# BSPD_002.net
KiCad netlist of a schematic drawn in Altium Designer
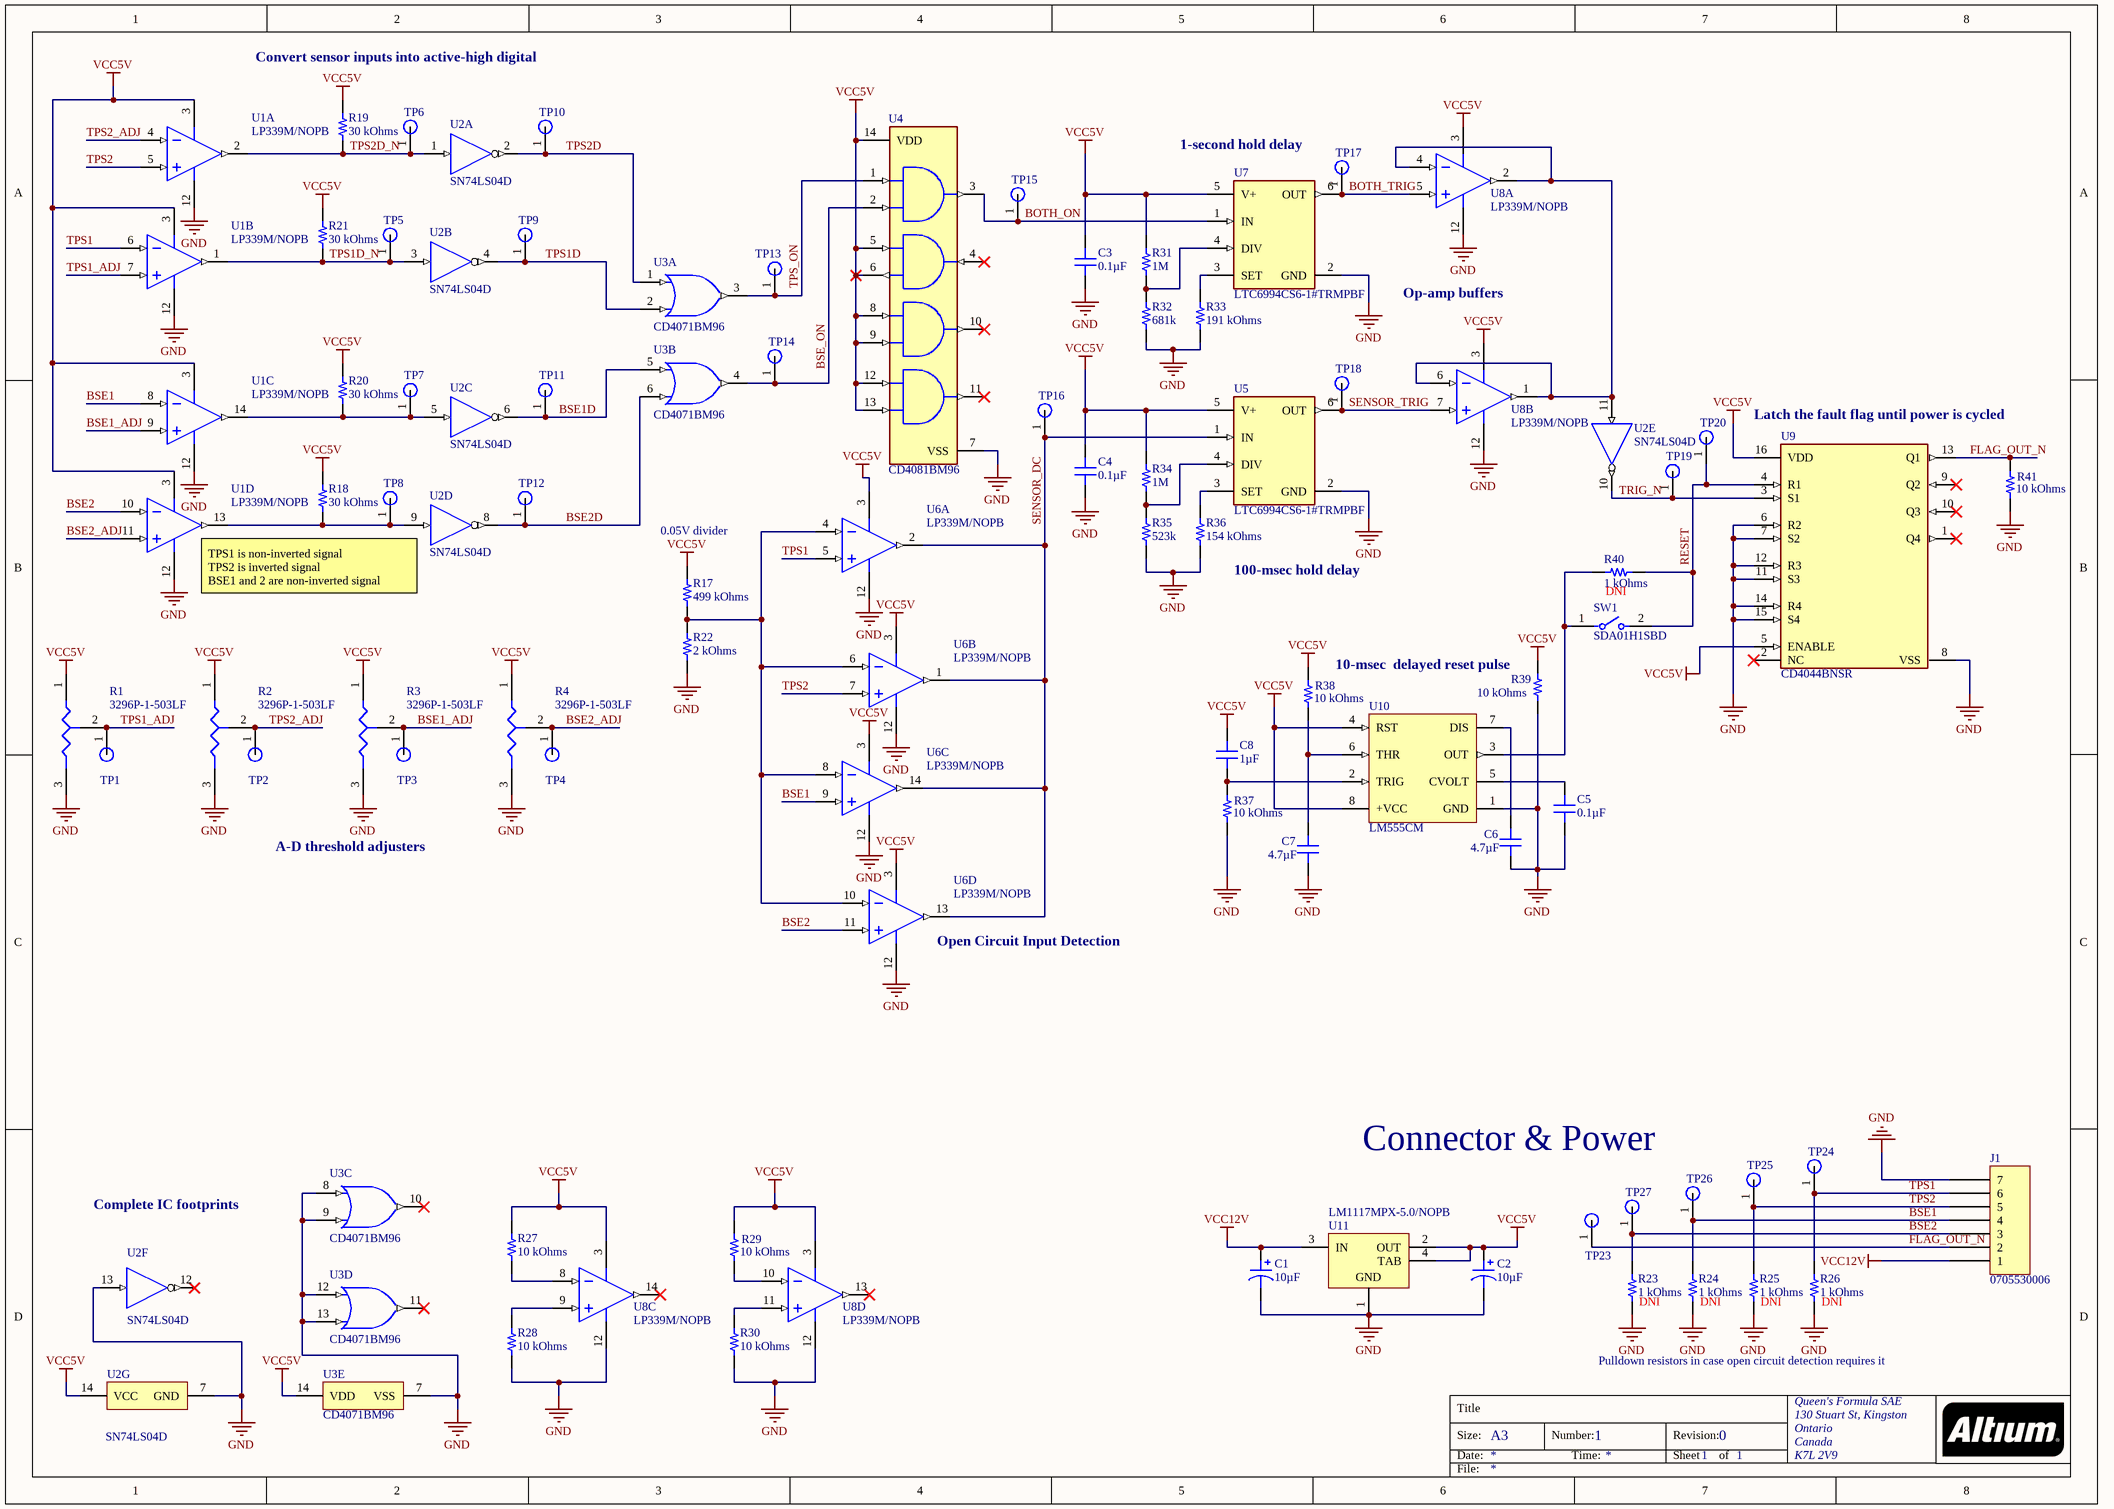
[diagram p0: BSPD_002.SchDoc]

(export (version "E")
  (design (tool "Eeschema 10.0.6"))
  (components
    (comp (ref "C1")
      (value "10µF")
      (footprint "CAP ALSMD 5.3MM H5.4MM")
      (description "CAP ALUM 10UF 20% 50V SMD")
      (fields
        (field (name "PART NUMBER") "EEE-1HA100WR")
        (field (name "MANUFACTURER") "Panasonic Electronic Components")
      )
      (libsource (lib "Celestial Altium Library - altium_library") (part "Polarised Capacitor"))
    )
    (comp (ref "C2")
      (value "10µF")
      (footprint "CAP ALSMD 5.3MM H5.4MM")
      (description "CAP ALUM 10UF 20% 50V SMD")
      (fields
        (field (name "PART NUMBER") "EEE-1HA100WR")
        (field (name "MANUFACTURER") "Panasonic Electronic Components")
      )
      (libsource (lib "Celestial Altium Library - altium_library") (part "Polarised Capacitor"))
    )
    (comp (ref "C3")
      (value "0.1µF")
      (footprint "CAP 0805_2012")
      (description "CAP CER 0.1UF 25V X7R 0805")
      (fields
        (field (name "PART NUMBER") "VJ0805Y104KXXCW1BC")
        (field (name "MANUFACTURER") "Vishay Vitramon")
      )
      (libsource (lib "Celestial Altium Library - altium_library") (part "Capacitor"))
    )
    (comp (ref "C4")
      (value "0.1µF")
      (footprint "CAP 0805_2012")
      (description "CAP CER 0.1UF 25V X7R 0805")
      (fields
        (field (name "PART NUMBER") "VJ0805Y104KXXCW1BC")
        (field (name "MANUFACTURER") "Vishay Vitramon")
      )
      (libsource (lib "Celestial Altium Library - altium_library") (part "Capacitor"))
    )
    (comp (ref "C5")
      (value "0.1µF")
      (footprint "CAP 0805_2012")
      (description "CAP CER 0.1UF 25V X7R 0805")
      (fields
        (field (name "PART NUMBER") "VJ0805Y104KXXCW1BC")
        (field (name "MANUFACTURER") "Vishay Vitramon")
      )
      (libsource (lib "Celestial Altium Library - altium_library") (part "Capacitor"))
    )
    (comp (ref "C6")
      (value "4.7µF")
      (footprint "CAP 0805_2012")
      (description "CAP CER 4.7UF 25V X5R 0805")
      (fields (field (name "PART NUMBER") "TMK212BBJ475KD-T") (field (name "MANUFACTURER") "Taiyo Yuden"))
      (libsource (lib "Celestial Altium Library - altium_library") (part "Capacitor"))
    )
    (comp (ref "C7")
      (value "4.7µF")
      (footprint "CAP 0805_2012")
      (description "CAP CER 4.7UF 25V X5R 0805")
      (fields (field (name "PART NUMBER") "TMK212BBJ475KD-T") (field (name "MANUFACTURER") "Taiyo Yuden"))
      (libsource (lib "Celestial Altium Library - altium_library") (part "Capacitor"))
    )
    (comp (ref "C8")
      (value "1µF")
      (footprint "CAP 0805_2012")
      (description "CAP CER 1UF 25V X7R 0805")
      (fields
        (field (name "PART NUMBER") "VJ0805Y105KXXTW1BC")
        (field (name "MANUFACTURER") "Vishay Vitramon")
      )
      (libsource (lib "Celestial Altium Library - altium_library") (part "Capacitor"))
    )
    (comp (ref "J1")
      (value "0705530006")
      (footprint "MOLEX SDA-70553-7PIN")
      (description "CONN HEADER R/A 7POS 2.54MM")
      (fields (field (name "MANUFACTURER") "Molex"))
      (libsource (lib "Celestial Altium Library - altium_library") (part "7 Pin"))
    )
    (comp (ref "R1")
      (value "3296P-1-503LF")
      (footprint "3296P-1-503LF-Footprint-1")
      (description "50k 10% Trimmer Potentiometer 25-Turn Cermet")
      (fields (field (name "TOLERANCE") "10%"))
      (libsource (lib "Queens University - FSAE") (part "3296P-1-503LF"))
    )
    (comp (ref "R2")
      (value "3296P-1-503LF")
      (footprint "3296P-1-503LF-Footprint-1")
      (description "50k 10% Trimmer Potentiometer 25-Turn Cermet")
      (fields (field (name "TOLERANCE") "10%"))
      (libsource (lib "Queens University - FSAE") (part "3296P-1-503LF"))
    )
    (comp (ref "R3")
      (value "3296P-1-503LF")
      (footprint "3296P-1-503LF-Footprint-1")
      (description "50k 10% Trimmer Potentiometer 25-Turn Cermet")
      (fields (field (name "TOLERANCE") "10%"))
      (libsource (lib "Queens University - FSAE") (part "3296P-1-503LF"))
    )
    (comp (ref "R4")
      (value "3296P-1-503LF")
      (footprint "3296P-1-503LF-Footprint-1")
      (description "50k 10% Trimmer Potentiometer 25-Turn Cermet")
      (fields (field (name "TOLERANCE") "10%"))
      (libsource (lib "Queens University - FSAE") (part "3296P-1-503LF"))
    )
    (comp (ref "R17")
      (value "499 kOhms")
      (footprint "RES 0805_2012")
      (description "RES SMD 499K OHM 1% 1/8W 0805")
      (fields (field (name "PART NUMBER") "RC0805FR-07499KL") (field (name "MANUFACTURER") "Yageo"))
      (libsource (lib "Celestial Altium Library - altium_library") (part "Resistor"))
    )
    (comp (ref "R18")
      (value "30 kOhms")
      (footprint "RES 0805_2012")
      (description "RES SMD 30K OHM 0.5% 1/8W 0805")
      (fields (field (name "PART NUMBER") "RT0805DRD0730KL") (field (name "MANUFACTURER") "Yageo"))
      (libsource (lib "Celestial Altium Library - altium_library") (part "Resistor"))
    )
    (comp (ref "R19")
      (value "30 kOhms")
      (footprint "RES 0805_2012")
      (description "RES SMD 30K OHM 0.5% 1/8W 0805")
      (fields (field (name "PART NUMBER") "RT0805DRD0730KL") (field (name "MANUFACTURER") "Yageo"))
      (libsource (lib "Celestial Altium Library - altium_library") (part "Resistor"))
    )
    (comp (ref "R20")
      (value "30 kOhms")
      (footprint "RES 0805_2012")
      (description "RES SMD 30K OHM 0.5% 1/8W 0805")
      (fields (field (name "PART NUMBER") "RT0805DRD0730KL") (field (name "MANUFACTURER") "Yageo"))
      (libsource (lib "Celestial Altium Library - altium_library") (part "Resistor"))
    )
    (comp (ref "R21")
      (value "30 kOhms")
      (footprint "RES 0805_2012")
      (description "RES SMD 30K OHM 0.5% 1/8W 0805")
      (fields (field (name "PART NUMBER") "RT0805DRD0730KL") (field (name "MANUFACTURER") "Yageo"))
      (libsource (lib "Celestial Altium Library - altium_library") (part "Resistor"))
    )
    (comp (ref "R22")
      (value "2 kOhms")
      (footprint "RES 0805_2012")
      (description "RES SMD 2K OHM 1% 1/8W 0805")
      (fields (field (name "PART NUMBER") "RC0805FR-072KL") (field (name "MANUFACTURER") "Yageo"))
      (libsource (lib "Celestial Altium Library - altium_library") (part "Resistor"))
    )
    (comp (ref "R23")
      (value "1 kOhms")
      (footprint "RES 0805_2012")
      (description "RES 1K OHM 0.1% 1/10W 0805")
      (fields
        (field (name "PART NUMBER") "RNCS0805BKE1K00")
        (field (name "MANUFACTURER") "Stackpole Electronics Inc")
      )
      (libsource (lib "Celestial Altium Library - altium_library") (part "Resistor"))
    )
    (comp (ref "R24")
      (value "1 kOhms")
      (footprint "RES 0805_2012")
      (description "RES 1K OHM 0.1% 1/10W 0805")
      (fields
        (field (name "PART NUMBER") "RNCS0805BKE1K00")
        (field (name "MANUFACTURER") "Stackpole Electronics Inc")
      )
      (libsource (lib "Celestial Altium Library - altium_library") (part "Resistor"))
    )
    (comp (ref "R25")
      (value "1 kOhms")
      (footprint "RES 0805_2012")
      (description "RES 1K OHM 0.1% 1/10W 0805")
      (fields
        (field (name "PART NUMBER") "RNCS0805BKE1K00")
        (field (name "MANUFACTURER") "Stackpole Electronics Inc")
      )
      (libsource (lib "Celestial Altium Library - altium_library") (part "Resistor"))
    )
    (comp (ref "R26")
      (value "1 kOhms")
      (footprint "RES 0805_2012")
      (description "RES 1K OHM 0.1% 1/10W 0805")
      (fields
        (field (name "PART NUMBER") "RNCS0805BKE1K00")
        (field (name "MANUFACTURER") "Stackpole Electronics Inc")
      )
      (libsource (lib "Celestial Altium Library - altium_library") (part "Resistor"))
    )
    (comp (ref "R27")
      (value "10 kOhms")
      (footprint "RES 0805_2012")
      (description "RES SMD 10K OHM 1% 1/8W 0805")
      (fields (field (name "PART NUMBER") "RC0805FR-0710KL") (field (name "MANUFACTURER") "Yageo"))
      (libsource (lib "Celestial Altium Library - altium_library") (part "Resistor"))
    )
    (comp (ref "R28")
      (value "10 kOhms")
      (footprint "RES 0805_2012")
      (description "RES SMD 10K OHM 1% 1/8W 0805")
      (fields (field (name "PART NUMBER") "RC0805FR-0710KL") (field (name "MANUFACTURER") "Yageo"))
      (libsource (lib "Celestial Altium Library - altium_library") (part "Resistor"))
    )
    (comp (ref "R29")
      (value "10 kOhms")
      (footprint "RES 0805_2012")
      (description "RES SMD 10K OHM 1% 1/8W 0805")
      (fields (field (name "PART NUMBER") "RC0805FR-0710KL") (field (name "MANUFACTURER") "Yageo"))
      (libsource (lib "Celestial Altium Library - altium_library") (part "Resistor"))
    )
    (comp (ref "R30")
      (value "10 kOhms")
      (footprint "RES 0805_2012")
      (description "RES SMD 10K OHM 1% 1/8W 0805")
      (fields (field (name "PART NUMBER") "RC0805FR-0710KL") (field (name "MANUFACTURER") "Yageo"))
      (libsource (lib "Celestial Altium Library - altium_library") (part "Resistor"))
    )
    (comp (ref "R31")
      (value "1M")
      (footprint "RES 0805_2012")
      (description "RES SMD 1M OHM 1% 1/8W 0805")
      (fields (field (name "PART NUMBER") "RC0805FR-071ML") (field (name "MANUFACTURER") "Yageo"))
      (libsource (lib "Celestial Altium Library - altium_library") (part "Resistor"))
    )
    (comp (ref "R32")
      (value "681k")
      (footprint "RES 0805_2012")
      (description "RES 681K OHM 1% 1/8W 0805")
      (fields
        (field (name "PART NUMBER") "RMCF0805FT681K")
        (field (name "MANUFACTURER") "Stackpole Electronics Inc")
      )
      (libsource (lib "Celestial Altium Library - altium_library") (part "Resistor"))
    )
    (comp (ref "R33")
      (value "191 kOhms")
      (footprint "RES 0805_2012")
      (description "RES SMD 191K OHM 1% 1/8W 0805")
      (fields (field (name "PART NUMBER") "RC0805FR-07191KL") (field (name "MANUFACTURER") "Yageo"))
      (libsource (lib "Celestial Altium Library - altium_library") (part "Resistor"))
    )
    (comp (ref "R34")
      (value "1M")
      (footprint "RES 0805_2012")
      (description "RES SMD 1M OHM 1% 1/8W 0805")
      (fields (field (name "PART NUMBER") "RC0805FR-071ML") (field (name "MANUFACTURER") "Yageo"))
      (libsource (lib "Celestial Altium Library - altium_library") (part "Resistor"))
    )
    (comp (ref "R35")
      (value "523k")
      (footprint "RES 0805_2012")
      (description "RES SMD 523K OHM 1% 1/8W 0805")
      (fields (field (name "PART NUMBER") "RC0805FR-07523KL") (field (name "MANUFACTURER") "Yageo"))
      (libsource (lib "Celestial Altium Library - altium_library") (part "Resistor"))
    )
    (comp (ref "R36")
      (value "154 kOhms")
      (footprint "RES 0805_2012")
      (description "RES SMD 154K OHM 1% 1/8W 0805")
      (fields (field (name "PART NUMBER") "RC0805FR-07154KL") (field (name "MANUFACTURER") "Yageo"))
      (libsource (lib "Celestial Altium Library - altium_library") (part "Resistor"))
    )
    (comp (ref "R37")
      (value "10 kOhms")
      (footprint "RES 0805_2012")
      (description "RES SMD 10K OHM 1% 1/8W 0805")
      (fields (field (name "PART NUMBER") "RC0805FR-0710KL") (field (name "MANUFACTURER") "Yageo"))
      (libsource (lib "Celestial Altium Library - altium_library") (part "Resistor"))
    )
    (comp (ref "R38")
      (value "10 kOhms")
      (footprint "RES 0805_2012")
      (description "RES SMD 10K OHM 1% 1/8W 0805")
      (fields (field (name "PART NUMBER") "RC0805FR-0710KL") (field (name "MANUFACTURER") "Yageo"))
      (libsource (lib "Celestial Altium Library - altium_library") (part "Resistor"))
    )
    (comp (ref "R39")
      (value "10 kOhms")
      (footprint "RES 0805_2012")
      (description "RES SMD 10K OHM 1% 1/8W 0805")
      (fields (field (name "PART NUMBER") "RC0805FR-0710KL") (field (name "MANUFACTURER") "Yageo"))
      (libsource (lib "Celestial Altium Library - altium_library") (part "Resistor"))
    )
    (comp (ref "R40")
      (value "1 kOhms")
      (footprint "RES 0805_2012")
      (description "RES 1K OHM 0.1% 1/10W 0805")
      (fields
        (field (name "PART NUMBER") "RNCS0805BKE1K00")
        (field (name "MANUFACTURER") "Stackpole Electronics Inc")
      )
      (libsource (lib "Celestial Altium Library - altium_library") (part "Resistor"))
    )
    (comp (ref "R41")
      (value "10 kOhms")
      (footprint "RES 0805_2012")
      (description "RES SMD 10K OHM 1% 1/8W 0805")
      (fields (field (name "PART NUMBER") "RC0805FR-0710KL") (field (name "MANUFACTURER") "Yageo"))
      (libsource (lib "Celestial Altium Library - altium_library") (part "Resistor"))
    )
    (comp (ref "SW1")
      (value "SDA01H1SBD")
      (footprint "FP-SDA01H1SBD-MFG")
      (description "Switch DIP OFF ON SPST 1 Raised Slide 0.1A 24VDC Gull Wing 1000Cycles SMD Tube")
      (libsource (lib "Queens University - FSAE") (part "bb27bde45df87f1f469753f287ef5ae"))
    )
    (comp (ref "TP1") (value "Test Point") (footprint "TP1") (libsource (lib "ethan") (part "TP1")))
    (comp (ref "TP2") (value "Test Point") (footprint "TP1") (libsource (lib "ethan") (part "TP1")))
    (comp (ref "TP3") (value "Test Point") (footprint "TP1") (libsource (lib "ethan") (part "TP1")))
    (comp (ref "TP4") (value "Test Point") (footprint "TP1") (libsource (lib "ethan") (part "TP1")))
    (comp (ref "TP5") (value "Test Point") (footprint "TP1") (libsource (lib "ethan") (part "TP1")))
    (comp (ref "TP6") (value "Test Point") (footprint "TP1") (libsource (lib "ethan") (part "TP1")))
    (comp (ref "TP7") (value "Test Point") (footprint "TP1") (libsource (lib "ethan") (part "TP1")))
    (comp (ref "TP8") (value "Test Point") (footprint "TP1") (libsource (lib "ethan") (part "TP1")))
    (comp (ref "TP9") (value "Test Point") (footprint "TP1") (libsource (lib "ethan") (part "TP1")))
    (comp (ref "TP10") (value "Test Point") (footprint "TP1") (libsource (lib "ethan") (part "TP1")))
    (comp (ref "TP11") (value "Test Point") (footprint "TP1") (libsource (lib "ethan") (part "TP1")))
    (comp (ref "TP12") (value "Test Point") (footprint "TP1") (libsource (lib "ethan") (part "TP1")))
    (comp (ref "TP13") (value "Test Point") (footprint "TP1") (libsource (lib "ethan") (part "TP1")))
    (comp (ref "TP14") (value "Test Point") (footprint "TP1") (libsource (lib "ethan") (part "TP1")))
    (comp (ref "TP15") (value "Test Point") (footprint "TP1") (libsource (lib "ethan") (part "TP1")))
    (comp (ref "TP16") (value "Test Point") (footprint "TP1") (libsource (lib "ethan") (part "TP1")))
    (comp (ref "TP17") (value "Test Point") (footprint "TP1") (libsource (lib "ethan") (part "TP1")))
    (comp (ref "TP18") (value "Test Point") (footprint "TP1") (libsource (lib "ethan") (part "TP1")))
    (comp (ref "TP19") (value "Test Point") (footprint "TP1") (libsource (lib "ethan") (part "TP1")))
    (comp (ref "TP20") (value "Test Point") (footprint "TP1") (libsource (lib "ethan") (part "TP1")))
    (comp (ref "TP23") (value "Test Point") (footprint "TP1") (libsource (lib "ethan") (part "TP1")))
    (comp (ref "TP24") (value "Test Point") (footprint "TP1") (libsource (lib "ethan") (part "TP1")))
    (comp (ref "TP25") (value "Test Point") (footprint "TP1") (libsource (lib "ethan") (part "TP1")))
    (comp (ref "TP26") (value "Test Point") (footprint "TP1") (libsource (lib "ethan") (part "TP1")))
    (comp (ref "TP27") (value "Test Point") (footprint "TP1") (libsource (lib "ethan") (part "TP1")))
    (comp (ref "U1")
      (value "LP339M/NOPB")
      (footprint "D0014A_L")
      (description "TEXAS INSTRUMENTS   LP339M/NOPB   LOW POWER COMPARATOR, QUAD, 8 uS, SOIC-14")
      (libsource (lib "Queens University - FSAE") (part "AN-COMP-LP339-14"))
    )
    (comp (ref "U2")
      (value "SN74LS04D")
      (footprint "D0014A_L")
      (description "TEXAS INSTRUMENTS - SN74LS04D - HEX INVERTER, SMD, 74LS04, SOIC14")
      (libsource (lib "Queens University - FSAE") (part "TI-CD_SNX4XXXXXX4X_19A-14"))
    )
    (comp (ref "U3")
      (value "CD4071BM96")
      (footprint "D0014A_L")
      (description "OR Gate 4-Element 2-IN CMOS 14-Pin SOIC T/R")
      (libsource (lib "Queens University - FSAE") (part "TI-CD4071B-14"))
    )
    (comp (ref "U4")
      (value "CD4081BM96")
      (footprint "FP-D0014A-MFG")
      (description "TEXAS INSTRUMENTS - CD4081BM96 - AND Gate, CD4081, 8 Input, 6.8 mA, 3 V to 18 V, SOIC-14")
      (libsource (lib "Queens University - FSAE") (part "72f76806fbbab040b8a954f50d4bcdd"))
    )
    (comp (ref "U5")
      (value "LTC6994CS6-1#TRMPBF")
      (footprint "FP-S6-6-05-08-1636-MFG")
      (description "Programmable Delay Block 6-Pin TSOT-23 T/R")
      (libsource (lib "Queens University - FSAE") (part "9980ea3ec28f5fc7ab7b696581a065a"))
    )
    (comp (ref "U6")
      (value "LP339M/NOPB")
      (footprint "D0014A_L")
      (description "TEXAS INSTRUMENTS   LP339M/NOPB   LOW POWER COMPARATOR, QUAD, 8 uS, SOIC-14")
      (libsource (lib "Queens University - FSAE") (part "AN-COMP-LP339-14"))
    )
    (comp (ref "U7")
      (value "LTC6994CS6-1#TRMPBF")
      (footprint "FP-S6-6-05-08-1636-MFG")
      (description "Programmable Delay Block 6-Pin TSOT-23 T/R")
      (libsource (lib "Queens University - FSAE") (part "9980ea3ec28f5fc7ab7b696581a065a"))
    )
    (comp (ref "U8")
      (value "LP339M/NOPB")
      (footprint "D0014A_L")
      (description "TEXAS INSTRUMENTS   LP339M/NOPB   LOW POWER COMPARATOR, QUAD, 8 uS, SOIC-14")
      (libsource (lib "Queens University - FSAE") (part "AN-COMP-LP339-14"))
    )
    (comp (ref "U9")
      (value "CD4044BNSR")
      (footprint "FP-D0016A-MFG")
      (libsource (lib "Queens University - FSAE") (part "b654bc9f5570033e531f2d9d884d1b2"))
    )
    (comp (ref "U10")
      (value "LM555CM")
      (footprint "D0008A_L")
      (description "IC OSC SGL TIMER 100KHZ 8-SOIC")
      (libsource (lib "Queens University - FSAE") (part "AN-TIMER-LM555-8"))
    )
    (comp (ref "U11")
      (value "LM1117MPX-5.0/NOPB")
      (footprint "DCY0004A_M")
      (description "800-mA 15-V linear voltage regulator 4-SOT-223 0 to 125")
      (libsource (lib "Queens University - FSAE") (part "PM-REG-LM1086-SOT4"))
    )
  )
  (nets
    (net (code "1") (name "/BOTH_ON") (class "Default")
      (node (ref "TP15") (pin "1") (pinfunction "1_1") (pintype "passive"))
      (node (ref "U4") (pin "3") (pinfunction "J_3") (pintype "output"))
      (node (ref "U7") (pin "1") (pinfunction "IN_1") (pintype "input"))
    )
    (net (code "2") (name "/BOTH_TRIG") (class "Default")
      (node (ref "TP17") (pin "1") (pinfunction "1_1") (pintype "passive"))
      (node (ref "U7") (pin "6") (pinfunction "OUT_6") (pintype "output"))
      (node (ref "U8") (pin "5") (pinfunction "IN1+_5") (pintype "input"))
    )
    (net (code "3") (name "/BSE1") (class "Default")
      (node (ref "J1") (pin "4") (pinfunction "4_4") (pintype "passive"))
      (node (ref "R24") (pin "2") (pinfunction "2_2") (pintype "passive"))
      (node (ref "TP26") (pin "1") (pinfunction "1_1") (pintype "passive"))
      (node (ref "U1") (pin "8") (pinfunction "IN3-_8") (pintype "input"))
      (node (ref "U6") (pin "9") (pinfunction "IN3+_9") (pintype "input"))
    )
    (net (code "4") (name "/BSE1D") (class "Default")
      (node (ref "TP11") (pin "1") (pinfunction "1_1") (pintype "passive"))
      (node (ref "U2") (pin "6") (pinfunction "~{3Y}_6") (pintype "output"))
      (node (ref "U3") (pin "5") (pinfunction "C_5") (pintype "input"))
    )
    (net (code "5") (name "/BSE1_ADJ") (class "Default")
      (node (ref "R3") (pin "2") (pinfunction "TAP_2") (pintype "passive"))
      (node (ref "TP3") (pin "1") (pinfunction "1_1") (pintype "passive"))
      (node (ref "U1") (pin "9") (pinfunction "IN3+_9") (pintype "input"))
    )
    (net (code "6") (name "/BSE2") (class "Default")
      (node (ref "J1") (pin "3") (pinfunction "3_3") (pintype "passive"))
      (node (ref "R23") (pin "2") (pinfunction "2_2") (pintype "passive"))
      (node (ref "TP27") (pin "1") (pinfunction "1_1") (pintype "passive"))
      (node (ref "U1") (pin "10") (pinfunction "IN4-_10") (pintype "input"))
      (node (ref "U6") (pin "11") (pinfunction "IN4+_11") (pintype "input"))
    )
    (net (code "7") (name "/BSE2D") (class "Default")
      (node (ref "TP12") (pin "1") (pinfunction "1_1") (pintype "passive"))
      (node (ref "U2") (pin "8") (pinfunction "~{4Y}_8") (pintype "output"))
      (node (ref "U3") (pin "6") (pinfunction "D_6") (pintype "input"))
    )
    (net (code "8") (name "/BSE2_ADJ") (class "Default")
      (node (ref "R4") (pin "2") (pinfunction "TAP_2") (pintype "passive"))
      (node (ref "TP4") (pin "1") (pinfunction "1_1") (pintype "passive"))
      (node (ref "U1") (pin "11") (pinfunction "IN4+_11") (pintype "input"))
    )
    (net (code "9") (name "/BSE_ON") (class "Default")
      (node (ref "TP14") (pin "1") (pinfunction "1_1") (pintype "passive"))
      (node (ref "U3") (pin "4") (pinfunction "K_4") (pintype "output"))
      (node (ref "U4") (pin "2") (pinfunction "B_2") (pintype "input"))
    )
    (net (code "10") (name "/FLAG_OUT_N") (class "Default")
      (node (ref "J1") (pin "2") (pinfunction "2_2") (pintype "passive"))
      (node (ref "R41") (pin "2") (pinfunction "2_2") (pintype "passive"))
      (node (ref "TP23") (pin "1") (pinfunction "1_1") (pintype "passive"))
      (node (ref "U9") (pin "13") (pinfunction "Q1_13") (pintype "output"))
    )
    (net (code "11") (name "/RESET") (class "Default")
      (node (ref "R40") (pin "1") (pinfunction "1_1") (pintype "passive"))
      (node (ref "SW1") (pin "2") (pinfunction "2_2") (pintype "passive"))
      (node (ref "TP20") (pin "1") (pinfunction "1_1") (pintype "passive"))
      (node (ref "U9") (pin "4") (pinfunction "R1_4") (pintype "input"))
    )
    (net (code "12") (name "/SENSOR_DC") (class "Default")
      (node (ref "TP16") (pin "1") (pinfunction "1_1") (pintype "passive"))
      (node (ref "U5") (pin "1") (pinfunction "IN_1") (pintype "input"))
      (node (ref "U6") (pin "1") (pinfunction "OUT2_1") (pintype "output"))
      (node (ref "U6") (pin "13") (pinfunction "OUT4_13") (pintype "output"))
      (node (ref "U6") (pin "14") (pinfunction "OUT3_14") (pintype "output"))
      (node (ref "U6") (pin "2") (pinfunction "OUT1_2") (pintype "output"))
    )
    (net (code "13") (name "/SENSOR_TRIG") (class "Default")
      (node (ref "TP18") (pin "1") (pinfunction "1_1") (pintype "passive"))
      (node (ref "U5") (pin "6") (pinfunction "OUT_6") (pintype "output"))
      (node (ref "U8") (pin "7") (pinfunction "IN2+_7") (pintype "input"))
    )
    (net (code "14") (name "/TPS1") (class "Default")
      (node (ref "J1") (pin "6") (pinfunction "6_6") (pintype "passive"))
      (node (ref "R26") (pin "2") (pinfunction "2_2") (pintype "passive"))
      (node (ref "TP24") (pin "1") (pinfunction "1_1") (pintype "passive"))
      (node (ref "U1") (pin "6") (pinfunction "IN2-_6") (pintype "input"))
      (node (ref "U6") (pin "5") (pinfunction "IN1+_5") (pintype "input"))
    )
    (net (code "15") (name "/TPS1D") (class "Default")
      (node (ref "TP9") (pin "1") (pinfunction "1_1") (pintype "passive"))
      (node (ref "U2") (pin "4") (pinfunction "~{2Y}_4") (pintype "output"))
      (node (ref "U3") (pin "2") (pinfunction "B_2") (pintype "input"))
    )
    (net (code "16") (name "/TPS1D_N") (class "Default")
      (node (ref "R21") (pin "1") (pinfunction "1_1") (pintype "passive"))
      (node (ref "TP5") (pin "1") (pinfunction "1_1") (pintype "passive"))
      (node (ref "U1") (pin "1") (pinfunction "OUT2_1") (pintype "output"))
      (node (ref "U2") (pin "3") (pinfunction "2A_3") (pintype "input"))
    )
    (net (code "17") (name "/TPS1_ADJ") (class "Default")
      (node (ref "R1") (pin "2") (pinfunction "TAP_2") (pintype "passive"))
      (node (ref "TP1") (pin "1") (pinfunction "1_1") (pintype "passive"))
      (node (ref "U1") (pin "7") (pinfunction "IN2+_7") (pintype "input"))
    )
    (net (code "18") (name "/TPS2") (class "Default")
      (node (ref "J1") (pin "5") (pinfunction "5_5") (pintype "passive"))
      (node (ref "R25") (pin "2") (pinfunction "2_2") (pintype "passive"))
      (node (ref "TP25") (pin "1") (pinfunction "1_1") (pintype "passive"))
      (node (ref "U1") (pin "5") (pinfunction "IN1+_5") (pintype "input"))
      (node (ref "U6") (pin "7") (pinfunction "IN2+_7") (pintype "input"))
    )
    (net (code "19") (name "/TPS2D") (class "Default")
      (node (ref "TP10") (pin "1") (pinfunction "1_1") (pintype "passive"))
      (node (ref "U2") (pin "2") (pinfunction "~{1Y}_2") (pintype "output"))
      (node (ref "U3") (pin "1") (pinfunction "A_1") (pintype "input"))
    )
    (net (code "20") (name "/TPS2D_N") (class "Default")
      (node (ref "R19") (pin "1") (pinfunction "1_1") (pintype "passive"))
      (node (ref "TP6") (pin "1") (pinfunction "1_1") (pintype "passive"))
      (node (ref "U1") (pin "2") (pinfunction "OUT1_2") (pintype "output"))
      (node (ref "U2") (pin "1") (pinfunction "1A_1") (pintype "input"))
    )
    (net (code "21") (name "/TPS2_ADJ") (class "Default")
      (node (ref "R2") (pin "2") (pinfunction "TAP_2") (pintype "passive"))
      (node (ref "TP2") (pin "1") (pinfunction "1_1") (pintype "passive"))
      (node (ref "U1") (pin "4") (pinfunction "IN1-_4") (pintype "input"))
    )
    (net (code "22") (name "/TPS_ON") (class "Default")
      (node (ref "TP13") (pin "1") (pinfunction "1_1") (pintype "passive"))
      (node (ref "U3") (pin "3") (pinfunction "J_3") (pintype "output"))
      (node (ref "U4") (pin "1") (pinfunction "A_1") (pintype "input"))
    )
    (net (code "23") (name "/TRIG_N") (class "Default")
      (node (ref "TP19") (pin "1") (pinfunction "1_1") (pintype "passive"))
      (node (ref "U2") (pin "10") (pinfunction "~{5Y}_10") (pintype "output"))
      (node (ref "U9") (pin "3") (pinfunction "S1_3") (pintype "input"))
    )
    (net (code "24") (name "GND") (class "Default")
      (node (ref "C1") (pin "2") (pinfunction "2_2") (pintype "passive"))
      (node (ref "C2") (pin "2") (pinfunction "2_2") (pintype "passive"))
      (node (ref "C3") (pin "1") (pinfunction "1_1") (pintype "passive"))
      (node (ref "C4") (pin "1") (pinfunction "1_1") (pintype "passive"))
      (node (ref "C5") (pin "1") (pinfunction "1_1") (pintype "passive"))
      (node (ref "C6") (pin "2") (pinfunction "2_2") (pintype "passive"))
      (node (ref "C7") (pin "2") (pinfunction "2_2") (pintype "passive"))
      (node (ref "J1") (pin "7") (pinfunction "7_7") (pintype "passive"))
      (node (ref "R1") (pin "3") (pinfunction "B_3") (pintype "passive"))
      (node (ref "R2") (pin "3") (pinfunction "B_3") (pintype "passive"))
      (node (ref "R22") (pin "1") (pinfunction "1_1") (pintype "passive"))
      (node (ref "R23") (pin "1") (pinfunction "1_1") (pintype "passive"))
      (node (ref "R24") (pin "1") (pinfunction "1_1") (pintype "passive"))
      (node (ref "R25") (pin "1") (pinfunction "1_1") (pintype "passive"))
      (node (ref "R26") (pin "1") (pinfunction "1_1") (pintype "passive"))
      (node (ref "R28") (pin "1") (pinfunction "1_1") (pintype "passive"))
      (node (ref "R3") (pin "3") (pinfunction "B_3") (pintype "passive"))
      (node (ref "R30") (pin "1") (pinfunction "1_1") (pintype "passive"))
      (node (ref "R32") (pin "1") (pinfunction "1_1") (pintype "passive"))
      (node (ref "R33") (pin "1") (pinfunction "1_1") (pintype "passive"))
      (node (ref "R35") (pin "1") (pinfunction "1_1") (pintype "passive"))
      (node (ref "R36") (pin "1") (pinfunction "1_1") (pintype "passive"))
      (node (ref "R37") (pin "1") (pinfunction "1_1") (pintype "passive"))
      (node (ref "R39") (pin "1") (pinfunction "1_1") (pintype "passive"))
      (node (ref "R4") (pin "3") (pinfunction "B_3") (pintype "passive"))
      (node (ref "R41") (pin "1") (pinfunction "1_1") (pintype "passive"))
      (node (ref "U1") (pin "12") (pinfunction "GND_12") (pintype "power_in"))
      (node (ref "U10") (pin "1") (pinfunction "GND_1") (pintype "power_in"))
      (node (ref "U11") (pin "1") (pinfunction "GND_1") (pintype "power_in"))
      (node (ref "U2") (pin "13") (pinfunction "6A_13") (pintype "input"))
      (node (ref "U2") (pin "7") (pinfunction "GND_7") (pintype "power_in"))
      (node (ref "U3") (pin "12") (pinfunction "G_12") (pintype "input"))
      (node (ref "U3") (pin "13") (pinfunction "H_13") (pintype "input"))
      (node (ref "U3") (pin "7") (pinfunction "VSS_7") (pintype "power_in"))
      (node (ref "U3") (pin "8") (pinfunction "E_8") (pintype "input"))
      (node (ref "U3") (pin "9") (pinfunction "F_9") (pintype "input"))
      (node (ref "U4") (pin "7") (pinfunction "VSS_7") (pintype "power_in"))
      (node (ref "U5") (pin "2") (pinfunction "GND_2") (pintype "power_in"))
      (node (ref "U6") (pin "12") (pinfunction "GND_12") (pintype "power_in"))
      (node (ref "U7") (pin "2") (pinfunction "GND_2") (pintype "power_in"))
      (node (ref "U8") (pin "12") (pinfunction "GND_12") (pintype "power_in"))
      (node (ref "U9") (pin "11") (pinfunction "S3_11") (pintype "input"))
      (node (ref "U9") (pin "12") (pinfunction "R3_12") (pintype "input"))
      (node (ref "U9") (pin "14") (pinfunction "R4_14") (pintype "input"))
      (node (ref "U9") (pin "15") (pinfunction "S4_15") (pintype "input"))
      (node (ref "U9") (pin "6") (pinfunction "R2_6") (pintype "input"))
      (node (ref "U9") (pin "7") (pinfunction "S2_7") (pintype "input"))
      (node (ref "U9") (pin "8") (pinfunction "VSS_8") (pintype "power_in"))
    )
    (net (code "25") (name "Net-(U1C-OUT3)") (class "Default")
      (node (ref "R20") (pin "1") (pinfunction "1_1") (pintype "passive"))
      (node (ref "TP7") (pin "1") (pinfunction "1_1") (pintype "passive"))
      (node (ref "U1") (pin "14") (pinfunction "OUT3_14") (pintype "output"))
      (node (ref "U2") (pin "5") (pinfunction "3A_5") (pintype "input"))
    )
    (net (code "26") (name "Net-(U1D-OUT4)") (class "Default")
      (node (ref "R18") (pin "1") (pinfunction "1_1") (pintype "passive"))
      (node (ref "TP8") (pin "1") (pinfunction "1_1") (pintype "passive"))
      (node (ref "U1") (pin "13") (pinfunction "OUT4_13") (pintype "output"))
      (node (ref "U2") (pin "9") (pinfunction "4A_9") (pintype "input"))
    )
    (net (code "27") (name "Net-(U2E-5A)") (class "Default")
      (node (ref "U2") (pin "11") (pinfunction "5A_11") (pintype "input"))
      (node (ref "U8") (pin "1") (pinfunction "OUT2_1") (pintype "output"))
      (node (ref "U8") (pin "2") (pinfunction "OUT1_2") (pintype "output"))
      (node (ref "U8") (pin "4") (pinfunction "IN1-_4") (pintype "input"))
      (node (ref "U8") (pin "6") (pinfunction "IN2-_6") (pintype "input"))
    )
    (net (code "28") (name "Net-(U5-DIV)") (class "Default")
      (node (ref "R34") (pin "2") (pinfunction "2_2") (pintype "passive"))
      (node (ref "R35") (pin "2") (pinfunction "2_2") (pintype "passive"))
      (node (ref "U5") (pin "4") (pinfunction "DIV_4") (pintype "input"))
    )
    (net (code "29") (name "Net-(U5-SET)") (class "Default")
      (node (ref "R36") (pin "2") (pinfunction "2_2") (pintype "passive"))
      (node (ref "U5") (pin "3") (pinfunction "SET_3") (pintype "passive"))
    )
    (net (code "30") (name "Net-(U6A-IN1-)") (class "Default")
      (node (ref "R17") (pin "1") (pinfunction "1_1") (pintype "passive"))
      (node (ref "R22") (pin "2") (pinfunction "2_2") (pintype "passive"))
      (node (ref "U6") (pin "10") (pinfunction "IN4-_10") (pintype "input"))
      (node (ref "U6") (pin "4") (pinfunction "IN1-_4") (pintype "input"))
      (node (ref "U6") (pin "6") (pinfunction "IN2-_6") (pintype "input"))
      (node (ref "U6") (pin "8") (pinfunction "IN3-_8") (pintype "input"))
    )
    (net (code "31") (name "Net-(U7-DIV)") (class "Default")
      (node (ref "R31") (pin "2") (pinfunction "2_2") (pintype "passive"))
      (node (ref "R32") (pin "2") (pinfunction "2_2") (pintype "passive"))
      (node (ref "U7") (pin "4") (pinfunction "DIV_4") (pintype "input"))
    )
    (net (code "32") (name "Net-(U7-SET)") (class "Default")
      (node (ref "R33") (pin "2") (pinfunction "2_2") (pintype "passive"))
      (node (ref "U7") (pin "3") (pinfunction "SET_3") (pintype "passive"))
    )
    (net (code "33") (name "Net-(U8C-IN3+)") (class "Default")
      (node (ref "R28") (pin "2") (pinfunction "2_2") (pintype "passive"))
      (node (ref "U8") (pin "9") (pinfunction "IN3+_9") (pintype "input"))
    )
    (net (code "34") (name "Net-(U8C-IN3-)") (class "Default")
      (node (ref "R27") (pin "1") (pinfunction "1_1") (pintype "passive"))
      (node (ref "U8") (pin "8") (pinfunction "IN3-_8") (pintype "input"))
    )
    (net (code "35") (name "Net-(U8D-IN4+)") (class "Default")
      (node (ref "R30") (pin "2") (pinfunction "2_2") (pintype "passive"))
      (node (ref "U8") (pin "11") (pinfunction "IN4+_11") (pintype "input"))
    )
    (net (code "36") (name "Net-(U8D-IN4-)") (class "Default")
      (node (ref "R29") (pin "1") (pinfunction "1_1") (pintype "passive"))
      (node (ref "U8") (pin "10") (pinfunction "IN4-_10") (pintype "input"))
    )
    (net (code "37") (name "Net-(U10-CVOLT)") (class "Default")
      (node (ref "C5") (pin "2") (pinfunction "2_2") (pintype "passive"))
      (node (ref "U10") (pin "5") (pinfunction "CVOLT_5") (pintype "passive"))
    )
    (net (code "38") (name "Net-(U10-DIS)") (class "Default")
      (node (ref "C6") (pin "1") (pinfunction "1_1") (pintype "passive"))
      (node (ref "U10") (pin "7") (pinfunction "DIS_7") (pintype "open_collector"))
    )
    (net (code "39") (name "Net-(U10-OUT)") (class "Default")
      (node (ref "R40") (pin "2") (pinfunction "2_2") (pintype "passive"))
      (node (ref "SW1") (pin "1") (pinfunction "1_1") (pintype "passive"))
      (node (ref "U10") (pin "3") (pinfunction "OUT_3") (pintype "output"))
    )
    (net (code "40") (name "Net-(U10-THR)") (class "Default")
      (node (ref "C7") (pin "1") (pinfunction "1_1") (pintype "passive"))
      (node (ref "R38") (pin "1") (pinfunction "1_1") (pintype "passive"))
      (node (ref "U10") (pin "6") (pinfunction "THR_6") (pintype "input"))
    )
    (net (code "41") (name "Net-(U10-TRIG)") (class "Default")
      (node (ref "C8") (pin "1") (pinfunction "1_1") (pintype "passive"))
      (node (ref "R37") (pin "2") (pinfunction "2_2") (pintype "passive"))
      (node (ref "U10") (pin "2") (pinfunction "TRIG_2") (pintype "input"))
    )
    (net (code "42") (name "VCC5V") (class "Default")
      (node (ref "C2") (pin "1") (pinfunction "1_1") (pintype "passive"))
      (node (ref "C3") (pin "2") (pinfunction "2_2") (pintype "passive"))
      (node (ref "C4") (pin "2") (pinfunction "2_2") (pintype "passive"))
      (node (ref "C8") (pin "2") (pinfunction "2_2") (pintype "passive"))
      (node (ref "R1") (pin "1") (pinfunction "A_1") (pintype "passive"))
      (node (ref "R17") (pin "2") (pinfunction "2_2") (pintype "passive"))
      (node (ref "R18") (pin "2") (pinfunction "2_2") (pintype "passive"))
      (node (ref "R19") (pin "2") (pinfunction "2_2") (pintype "passive"))
      (node (ref "R2") (pin "1") (pinfunction "A_1") (pintype "passive"))
      (node (ref "R20") (pin "2") (pinfunction "2_2") (pintype "passive"))
      (node (ref "R21") (pin "2") (pinfunction "2_2") (pintype "passive"))
      (node (ref "R27") (pin "2") (pinfunction "2_2") (pintype "passive"))
      (node (ref "R29") (pin "2") (pinfunction "2_2") (pintype "passive"))
      (node (ref "R3") (pin "1") (pinfunction "A_1") (pintype "passive"))
      (node (ref "R31") (pin "1") (pinfunction "1_1") (pintype "passive"))
      (node (ref "R34") (pin "1") (pinfunction "1_1") (pintype "passive"))
      (node (ref "R38") (pin "2") (pinfunction "2_2") (pintype "passive"))
      (node (ref "R39") (pin "2") (pinfunction "2_2") (pintype "passive"))
      (node (ref "R4") (pin "1") (pinfunction "A_1") (pintype "passive"))
      (node (ref "U1") (pin "3") (pinfunction "V+_3") (pintype "power_in"))
      (node (ref "U10") (pin "4") (pinfunction "RST_4") (pintype "input"))
      (node (ref "U10") (pin "8") (pinfunction "+VCC_8") (pintype "power_in"))
      (node (ref "U11") (pin "2") (pinfunction "OUT_2") (pintype "power_in"))
      (node (ref "U11") (pin "4") (pinfunction "TAB_4") (pintype "power_in"))
      (node (ref "U2") (pin "14") (pinfunction "VCC_14") (pintype "power_in"))
      (node (ref "U3") (pin "14") (pinfunction "VDD_14") (pintype "power_in"))
      (node (ref "U4") (pin "12") (pinfunction "G_12") (pintype "input"))
      (node (ref "U4") (pin "13") (pinfunction "H_13") (pintype "input"))
      (node (ref "U4") (pin "14") (pinfunction "VDD_14") (pintype "power_in"))
      (node (ref "U4") (pin "5") (pinfunction "C_5") (pintype "input"))
      (node (ref "U4") (pin "6") (pinfunction "D_6") (pintype "output"))
      (node (ref "U4") (pin "8") (pinfunction "E_8") (pintype "input"))
      (node (ref "U4") (pin "9") (pinfunction "F_9") (pintype "input"))
      (node (ref "U5") (pin "5") (pinfunction "V+_5") (pintype "power_in"))
      (node (ref "U6") (pin "3") (pinfunction "V+_3") (pintype "power_in"))
      (node (ref "U7") (pin "5") (pinfunction "V+_5") (pintype "power_in"))
      (node (ref "U8") (pin "3") (pinfunction "V+_3") (pintype "power_in"))
      (node (ref "U9") (pin "16") (pinfunction "VDD_16") (pintype "power_in"))
      (node (ref "U9") (pin "5") (pinfunction "ENABLE_5") (pintype "input"))
    )
    (net (code "43") (name "VCC12V") (class "Default")
      (node (ref "C1") (pin "1") (pinfunction "1_1") (pintype "passive"))
      (node (ref "J1") (pin "1") (pinfunction "1_1") (pintype "passive"))
      (node (ref "U11") (pin "3") (pinfunction "IN_3") (pintype "power_in"))
    )
    (net (code "44") (name "unconnected-(U2F-~{6Y}-Pad12)") (class "Default")
      (node (ref "U2") (pin "12") (pinfunction "~{6Y}_12") (pintype "output+no_connect"))
    )
    (net (code "45") (name "unconnected-(U3C-L-Pad10)") (class "Default")
      (node (ref "U3") (pin "10") (pinfunction "L_10") (pintype "output+no_connect"))
    )
    (net (code "46") (name "unconnected-(U3D-M-Pad11)") (class "Default")
      (node (ref "U3") (pin "11") (pinfunction "M_11") (pintype "output+no_connect"))
    )
    (net (code "47") (name "unconnected-(U4-K-Pad4)") (class "Default")
      (node (ref "U4") (pin "4") (pinfunction "K_4") (pintype "input+no_connect"))
    )
    (net (code "48") (name "unconnected-(U4-L-Pad10)") (class "Default")
      (node (ref "U4") (pin "10") (pinfunction "L_10") (pintype "output+no_connect"))
    )
    (net (code "49") (name "unconnected-(U4-M-Pad11)") (class "Default")
      (node (ref "U4") (pin "11") (pinfunction "M_11") (pintype "output+no_connect"))
    )
    (net (code "50") (name "unconnected-(U8C-OUT3-Pad14)") (class "Default")
      (node (ref "U8") (pin "14") (pinfunction "OUT3_14") (pintype "output+no_connect"))
    )
    (net (code "51") (name "unconnected-(U8D-OUT4-Pad13)") (class "Default")
      (node (ref "U8") (pin "13") (pinfunction "OUT4_13") (pintype "output+no_connect"))
    )
    (net (code "52") (name "unconnected-(U9-NC-Pad2)") (class "Default")
      (node (ref "U9") (pin "2") (pinfunction "NC_2") (pintype "passive+no_connect"))
    )
    (net (code "53") (name "unconnected-(U9-Q2-Pad9)") (class "Default")
      (node (ref "U9") (pin "9") (pinfunction "Q2_9") (pintype "input+no_connect"))
    )
    (net (code "54") (name "unconnected-(U9-Q3-Pad10)") (class "Default")
      (node (ref "U9") (pin "10") (pinfunction "Q3_10") (pintype "input+no_connect"))
    )
    (net (code "55") (name "unconnected-(U9-Q4-Pad1)") (class "Default")
      (node (ref "U9") (pin "1") (pinfunction "Q4_1") (pintype "output+no_connect"))
    )
  )
)
